# Main.net
KiCad netlist of a schematic drawn in Altium Designer
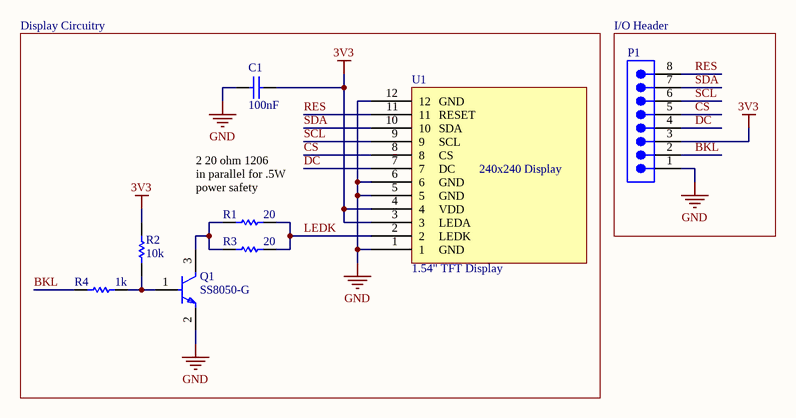
[diagram p0: Main.SchDoc]

(export (version "E")
  (design (tool "Eeschema 10.0.6"))
  (components
    (comp (ref "C1")
      (value "100nF")
      (footprint "CAPC1608X87X35NL15T15")
      (libsource (lib "Altium Content Vault") (part "CAP"))
    )
    (comp (ref "P1")
      (value "61300811121")
      (footprint "61300811121")
      (description "THT Vertical Pin Header WR-PHD, Pitch 2.54 mm, Single Row, 8 pins")
      (libsource (lib "Altium Content Vault") (part "Header_Male_1R_08P"))
    )
    (comp (ref "Q1")
      (value "SS8050-G")
      (footprint "FP-SS8050-G-MFG")
      (description "NPN TRANSISTOR 1.5A 40V SOT-23 R")
      (libsource (lib "Altium Content Vault") (part "2a1388f82443b098dcd57d24ac7632d"))
    )
    (comp (ref "R1")
      (value "20")
      (footprint "RESC3116X65X40NL10T20")
      (fields (field (name "MANUFACTURER") "Yageo") (field (name "PART NUMBER") "RC1206JR-0720RL"))
      (libsource (lib "Altium Content Vault") (part "RES"))
    )
    (comp (ref "R2")
      (value "10k")
      (footprint "RESC1608X55X25NL10T15")
      (fields (field (name "PART NUMBER") "RT0603BRE071KL") (field (name "MANUFACTURER") "Yageo"))
      (libsource (lib "Altium Content Vault") (part "RES"))
    )
    (comp (ref "R3")
      (value "20")
      (footprint "RESC3116X65X40NL10T20")
      (fields (field (name "MANUFACTURER") "Yageo") (field (name "PART NUMBER") "RC1206JR-0720RL"))
      (libsource (lib "Altium Content Vault") (part "RES"))
    )
    (comp (ref "R4")
      (value "1k")
      (footprint "RESC1608X55X25NL10T15")
      (fields (field (name "PART NUMBER") "RT0603BRE071KL") (field (name "MANUFACTURER") "Yageo"))
      (libsource (lib "Altium Content Vault") (part "RES"))
    )
    (comp (ref "U1")
      (value "1.54\" TFT Display")
      (footprint "PCBComponent_1")
      (libsource (lib "disp") (part "1.54{dblquote} TFT Display"))
    )
  )
  (nets
    (net (code "1") (name "/BKL") (class "Default")
      (node (ref "P1") (pin "2") (pinfunction "2_2") (pintype "passive"))
      (node (ref "R4") (pin "1") (pinfunction "1_1") (pintype "passive"))
    )
    (net (code "2") (name "/CS") (class "Default")
      (node (ref "P1") (pin "5") (pinfunction "5_5") (pintype "passive"))
      (node (ref "U1") (pin "8") (pinfunction "8_8") (pintype "passive"))
    )
    (net (code "3") (name "/DC") (class "Default")
      (node (ref "P1") (pin "4") (pinfunction "4_4") (pintype "passive"))
      (node (ref "U1") (pin "7") (pinfunction "7_7") (pintype "passive"))
    )
    (net (code "4") (name "/LEDK") (class "Default")
      (node (ref "R1") (pin "2") (pinfunction "2_2") (pintype "passive"))
      (node (ref "R3") (pin "2") (pinfunction "2_2") (pintype "passive"))
      (node (ref "U1") (pin "2") (pinfunction "2_2") (pintype "passive"))
    )
    (net (code "5") (name "/RES") (class "Default")
      (node (ref "P1") (pin "8") (pinfunction "8_8") (pintype "passive"))
      (node (ref "U1") (pin "11") (pinfunction "11_11") (pintype "passive"))
    )
    (net (code "6") (name "/SCL") (class "Default")
      (node (ref "P1") (pin "6") (pinfunction "6_6") (pintype "passive"))
      (node (ref "U1") (pin "9") (pinfunction "9_9") (pintype "passive"))
    )
    (net (code "7") (name "/SDA") (class "Default")
      (node (ref "P1") (pin "7") (pinfunction "7_7") (pintype "passive"))
      (node (ref "U1") (pin "10") (pinfunction "10_10") (pintype "passive"))
    )
    (net (code "8") (name "3V3") (class "Default")
      (node (ref "C1") (pin "1") (pinfunction "1_1") (pintype "passive"))
      (node (ref "P1") (pin "3") (pinfunction "3_3") (pintype "passive"))
      (node (ref "R2") (pin "2") (pinfunction "2_2") (pintype "passive"))
      (node (ref "U1") (pin "3") (pinfunction "3_3") (pintype "passive"))
      (node (ref "U1") (pin "4") (pinfunction "4_4") (pintype "passive"))
    )
    (net (code "9") (name "GND") (class "Default")
      (node (ref "C1") (pin "2") (pinfunction "2_2") (pintype "passive"))
      (node (ref "P1") (pin "1") (pinfunction "1_1") (pintype "passive"))
      (node (ref "Q1") (pin "2") (pinfunction "E_2") (pintype "passive"))
      (node (ref "U1") (pin "1") (pinfunction "1_1") (pintype "passive"))
      (node (ref "U1") (pin "12") (pinfunction "12_12") (pintype "passive"))
      (node (ref "U1") (pin "5") (pinfunction "5_5") (pintype "passive"))
      (node (ref "U1") (pin "6") (pinfunction "6_6") (pintype "passive"))
    )
    (net (code "10") (name "Net-(Q1-B)") (class "Default")
      (node (ref "Q1") (pin "1") (pinfunction "B_1") (pintype "passive"))
      (node (ref "R2") (pin "1") (pinfunction "1_1") (pintype "passive"))
      (node (ref "R4") (pin "2") (pinfunction "2_2") (pintype "passive"))
    )
    (net (code "11") (name "Net-(Q1-C)") (class "Default")
      (node (ref "Q1") (pin "3") (pinfunction "C_3") (pintype "passive"))
      (node (ref "R1") (pin "1") (pinfunction "1_1") (pintype "passive"))
      (node (ref "R3") (pin "1") (pinfunction "1_1") (pintype "passive"))
    )
  )
)
